# temp-stellwerk-a-3-autorouted.net
KiCad netlist of a schematic drawn in EAGLE
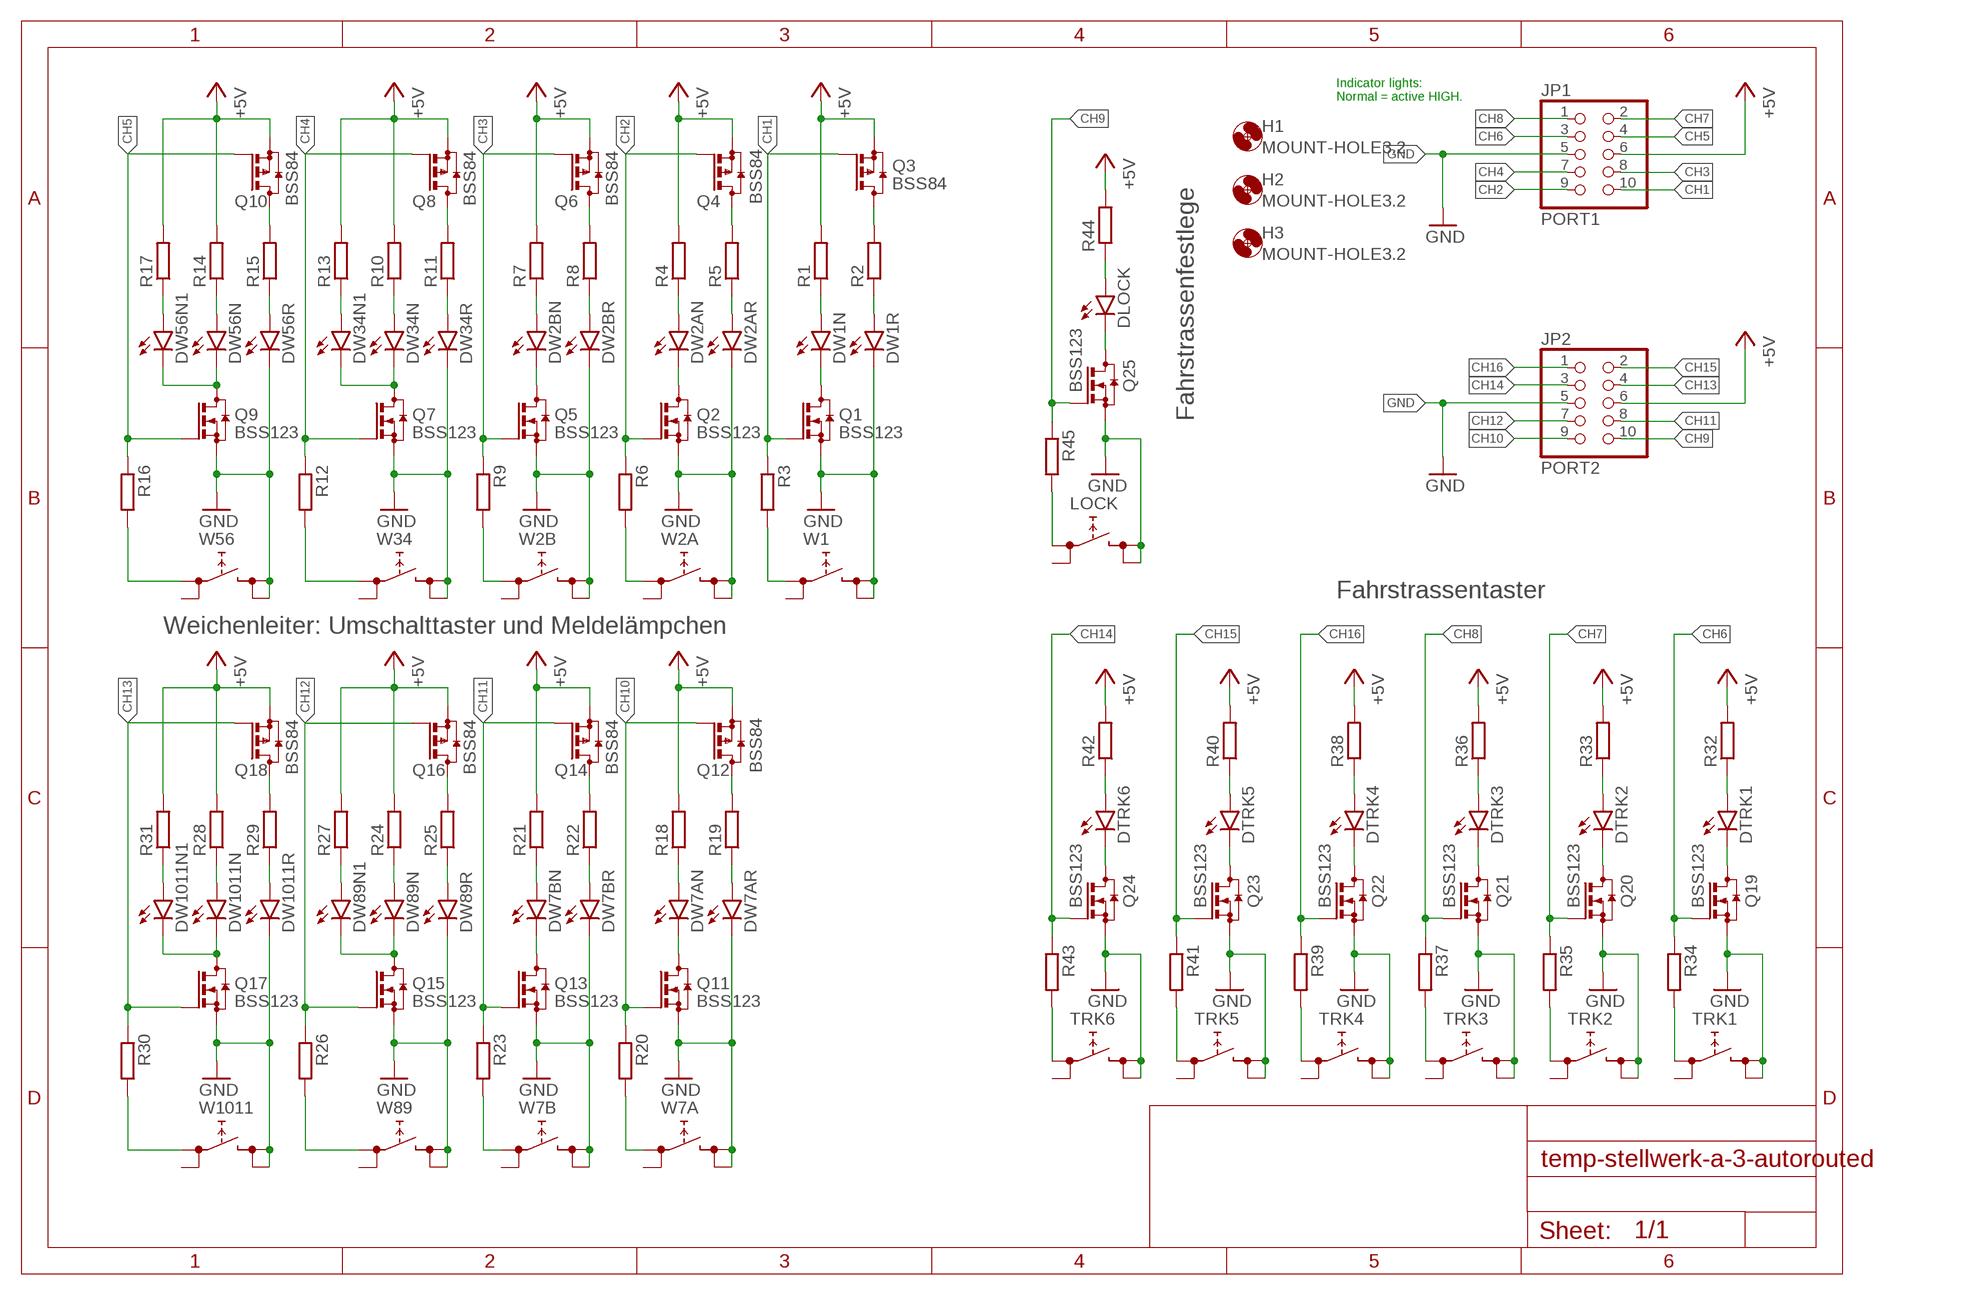
[diagram p0: schematic, sheet 1]

(export (version "E")
  (design (tool "Eeschema 10.0.6"))
  (components
    (comp (ref "DLOCK")
      (value "LEDCHIP-LED0805")
      (footprint "eagle-import:CHIP-LED0805")
      (libsource (lib "eagle-import") (part "LEDCHIP-LED0805"))
    )
    (comp (ref "DTRK1")
      (value "LEDCHIP-LED0805")
      (footprint "eagle-import:CHIP-LED0805")
      (libsource (lib "eagle-import") (part "LEDCHIP-LED0805"))
    )
    (comp (ref "DTRK2")
      (value "LEDCHIP-LED0805")
      (footprint "eagle-import:CHIP-LED0805")
      (libsource (lib "eagle-import") (part "LEDCHIP-LED0805"))
    )
    (comp (ref "DTRK3")
      (value "LEDCHIP-LED0805")
      (footprint "eagle-import:CHIP-LED0805")
      (libsource (lib "eagle-import") (part "LEDCHIP-LED0805"))
    )
    (comp (ref "DTRK4")
      (value "LEDCHIP-LED0805")
      (footprint "eagle-import:CHIP-LED0805")
      (libsource (lib "eagle-import") (part "LEDCHIP-LED0805"))
    )
    (comp (ref "DTRK5")
      (value "LEDCHIP-LED0805")
      (footprint "eagle-import:CHIP-LED0805")
      (libsource (lib "eagle-import") (part "LEDCHIP-LED0805"))
    )
    (comp (ref "DTRK6")
      (value "LEDCHIP-LED0805")
      (footprint "eagle-import:CHIP-LED0805")
      (libsource (lib "eagle-import") (part "LEDCHIP-LED0805"))
    )
    (comp (ref "DW1N")
      (value "LEDCHIP-LED0603")
      (footprint "eagle-import:CHIP-LED0603")
      (libsource (lib "eagle-import") (part "LEDCHIP-LED0603"))
    )
    (comp (ref "DW1R")
      (value "LEDCHIP-LED0603")
      (footprint "eagle-import:CHIP-LED0603")
      (libsource (lib "eagle-import") (part "LEDCHIP-LED0603"))
    )
    (comp (ref "DW2AN")
      (value "LEDCHIP-LED0603")
      (footprint "eagle-import:CHIP-LED0603")
      (libsource (lib "eagle-import") (part "LEDCHIP-LED0603"))
    )
    (comp (ref "DW2AR")
      (value "LEDCHIP-LED0603")
      (footprint "eagle-import:CHIP-LED0603")
      (libsource (lib "eagle-import") (part "LEDCHIP-LED0603"))
    )
    (comp (ref "DW2BN")
      (value "LEDCHIP-LED0805")
      (footprint "eagle-import:CHIP-LED0805")
      (libsource (lib "eagle-import") (part "LEDCHIP-LED0805"))
    )
    (comp (ref "DW2BR")
      (value "LEDCHIP-LED0805")
      (footprint "eagle-import:CHIP-LED0805")
      (libsource (lib "eagle-import") (part "LEDCHIP-LED0805"))
    )
    (comp (ref "DW7AN")
      (value "LEDCHIPLED_0603")
      (footprint "eagle-import:CHIPLED_0603")
      (libsource (lib "eagle-import") (part "LEDCHIPLED_0603"))
    )
    (comp (ref "DW7AR")
      (value "LEDCHIP-LED0603")
      (footprint "eagle-import:CHIP-LED0603")
      (libsource (lib "eagle-import") (part "LEDCHIP-LED0603"))
    )
    (comp (ref "DW7BN")
      (value "LEDCHIP-LED0805")
      (footprint "eagle-import:CHIP-LED0805")
      (libsource (lib "eagle-import") (part "LEDCHIP-LED0805"))
    )
    (comp (ref "DW7BR")
      (value "LEDCHIP-LED0805")
      (footprint "eagle-import:CHIP-LED0805")
      (libsource (lib "eagle-import") (part "LEDCHIP-LED0805"))
    )
    (comp (ref "DW34N")
      (value "LEDCHIP-LED0805")
      (footprint "eagle-import:CHIP-LED0805")
      (libsource (lib "eagle-import") (part "LEDCHIP-LED0805"))
    )
    (comp (ref "DW34N1")
      (value "LEDCHIP-LED0805")
      (footprint "eagle-import:CHIP-LED0805")
      (libsource (lib "eagle-import") (part "LEDCHIP-LED0805"))
    )
    (comp (ref "DW34R")
      (value "LEDCHIP-LED0805")
      (footprint "eagle-import:CHIP-LED0805")
      (libsource (lib "eagle-import") (part "LEDCHIP-LED0805"))
    )
    (comp (ref "DW56N")
      (value "LEDCHIP-LED0805")
      (footprint "eagle-import:CHIP-LED0805")
      (libsource (lib "eagle-import") (part "LEDCHIP-LED0805"))
    )
    (comp (ref "DW56N1")
      (value "LEDCHIP-LED0805")
      (footprint "eagle-import:CHIP-LED0805")
      (libsource (lib "eagle-import") (part "LEDCHIP-LED0805"))
    )
    (comp (ref "DW56R")
      (value "LEDCHIP-LED0805")
      (footprint "eagle-import:CHIP-LED0805")
      (libsource (lib "eagle-import") (part "LEDCHIP-LED0805"))
    )
    (comp (ref "DW89N")
      (value "LEDCHIP-LED0805")
      (footprint "eagle-import:CHIP-LED0805")
      (libsource (lib "eagle-import") (part "LEDCHIP-LED0805"))
    )
    (comp (ref "DW89N1")
      (value "LEDCHIP-LED0805")
      (footprint "eagle-import:CHIP-LED0805")
      (libsource (lib "eagle-import") (part "LEDCHIP-LED0805"))
    )
    (comp (ref "DW89R")
      (value "LEDCHIP-LED0805")
      (footprint "eagle-import:CHIP-LED0805")
      (libsource (lib "eagle-import") (part "LEDCHIP-LED0805"))
    )
    (comp (ref "DW1011N")
      (value "LEDCHIP-LED0805")
      (footprint "eagle-import:CHIP-LED0805")
      (libsource (lib "eagle-import") (part "LEDCHIP-LED0805"))
    )
    (comp (ref "DW1011N1")
      (value "LEDCHIP-LED0805")
      (footprint "eagle-import:CHIP-LED0805")
      (libsource (lib "eagle-import") (part "LEDCHIP-LED0805"))
    )
    (comp (ref "DW1011R")
      (value "LEDCHIP-LED0805")
      (footprint "eagle-import:CHIP-LED0805")
      (libsource (lib "eagle-import") (part "LEDCHIP-LED0805"))
    )
    (comp (ref "H1")
      (value "MOUNT-HOLE3.2")
      (footprint "eagle-import:3,2")
      (libsource (lib "eagle-import") (part "MOUNT-HOLE3.2"))
    )
    (comp (ref "H2")
      (value "MOUNT-HOLE3.2")
      (footprint "eagle-import:3,2")
      (libsource (lib "eagle-import") (part "MOUNT-HOLE3.2"))
    )
    (comp (ref "H3")
      (value "MOUNT-HOLE3.2")
      (footprint "eagle-import:3,2")
      (libsource (lib "eagle-import") (part "MOUNT-HOLE3.2"))
    )
    (comp (ref "JP1")
      (value "PORT1")
      (footprint "eagle-import:CON10M")
      (libsource (lib "eagle-import") (part "PINHD-2X5CN"))
    )
    (comp (ref "JP2")
      (value "PORT2")
      (footprint "eagle-import:CON10M")
      (libsource (lib "eagle-import") (part "PINHD-2X5CN"))
    )
    (comp (ref "LOCK")
      (value "LOCK")
      (footprint "eagle-import:TACTSW-6X6")
      (libsource (lib "eagle-import") (part "TACTSW-6X6S"))
    )
    (comp (ref "Q1")
      (value "BSS123")
      (footprint "eagle-import:SOT23-NCH")
      (libsource (lib "eagle-import") (part "BSS123"))
    )
    (comp (ref "Q2")
      (value "BSS123")
      (footprint "eagle-import:SOT23-NCH")
      (libsource (lib "eagle-import") (part "BSS123"))
    )
    (comp (ref "Q3")
      (value "BSS84")
      (footprint "eagle-import:SOT23")
      (libsource (lib "eagle-import") (part "BSS84"))
    )
    (comp (ref "Q4")
      (value "BSS84")
      (footprint "eagle-import:SOT23")
      (libsource (lib "eagle-import") (part "BSS84"))
    )
    (comp (ref "Q5")
      (value "BSS123")
      (footprint "eagle-import:SOT23-NCH")
      (libsource (lib "eagle-import") (part "BSS123"))
    )
    (comp (ref "Q6")
      (value "BSS84")
      (footprint "eagle-import:SOT23")
      (libsource (lib "eagle-import") (part "BSS84"))
    )
    (comp (ref "Q7")
      (value "BSS123")
      (footprint "eagle-import:SOT23-NCH")
      (libsource (lib "eagle-import") (part "BSS123"))
    )
    (comp (ref "Q8")
      (value "BSS84")
      (footprint "eagle-import:SOT23")
      (libsource (lib "eagle-import") (part "BSS84"))
    )
    (comp (ref "Q9")
      (value "BSS123")
      (footprint "eagle-import:SOT23-NCH")
      (libsource (lib "eagle-import") (part "BSS123"))
    )
    (comp (ref "Q10")
      (value "BSS84")
      (footprint "eagle-import:SOT23")
      (libsource (lib "eagle-import") (part "BSS84"))
    )
    (comp (ref "Q11")
      (value "BSS123")
      (footprint "eagle-import:SOT23-NCH")
      (libsource (lib "eagle-import") (part "BSS123"))
    )
    (comp (ref "Q12")
      (value "BSS84")
      (footprint "eagle-import:SOT23")
      (libsource (lib "eagle-import") (part "BSS84"))
    )
    (comp (ref "Q13")
      (value "BSS123")
      (footprint "eagle-import:SOT23-NCH")
      (libsource (lib "eagle-import") (part "BSS123"))
    )
    (comp (ref "Q14")
      (value "BSS84")
      (footprint "eagle-import:SOT23")
      (libsource (lib "eagle-import") (part "BSS84"))
    )
    (comp (ref "Q15")
      (value "BSS123")
      (footprint "eagle-import:SOT23-NCH")
      (libsource (lib "eagle-import") (part "BSS123"))
    )
    (comp (ref "Q16")
      (value "BSS84")
      (footprint "eagle-import:SOT23")
      (libsource (lib "eagle-import") (part "BSS84"))
    )
    (comp (ref "Q17")
      (value "BSS123")
      (footprint "eagle-import:SOT23-NCH")
      (libsource (lib "eagle-import") (part "BSS123"))
    )
    (comp (ref "Q18")
      (value "BSS84")
      (footprint "eagle-import:SOT23")
      (libsource (lib "eagle-import") (part "BSS84"))
    )
    (comp (ref "Q19")
      (value "BSS123")
      (footprint "eagle-import:SOT23-NCH")
      (libsource (lib "eagle-import") (part "BSS123"))
    )
    (comp (ref "Q20")
      (value "BSS123")
      (footprint "eagle-import:SOT23-NCH")
      (libsource (lib "eagle-import") (part "BSS123"))
    )
    (comp (ref "Q21")
      (value "BSS123")
      (footprint "eagle-import:SOT23-NCH")
      (libsource (lib "eagle-import") (part "BSS123"))
    )
    (comp (ref "Q22")
      (value "BSS123")
      (footprint "eagle-import:SOT23-NCH")
      (libsource (lib "eagle-import") (part "BSS123"))
    )
    (comp (ref "Q23")
      (value "BSS123")
      (footprint "eagle-import:SOT23-NCH")
      (libsource (lib "eagle-import") (part "BSS123"))
    )
    (comp (ref "Q24")
      (value "BSS123")
      (footprint "eagle-import:SOT23-NCH")
      (libsource (lib "eagle-import") (part "BSS123"))
    )
    (comp (ref "Q25")
      (value "BSS123")
      (footprint "eagle-import:SOT23-NCH")
      (libsource (lib "eagle-import") (part "BSS123"))
    )
    (comp (ref "R1")
      (value "R-EU_R0805")
      (footprint "eagle-import:R0805")
      (libsource (lib "eagle-import") (part "R-EU_R0805"))
    )
    (comp (ref "R2")
      (value "R-EU_R0805")
      (footprint "eagle-import:R0805")
      (libsource (lib "eagle-import") (part "R-EU_R0805"))
    )
    (comp (ref "R3")
      (value "R-EU_R0805")
      (footprint "eagle-import:R0805")
      (libsource (lib "eagle-import") (part "R-EU_R0805"))
    )
    (comp (ref "R4")
      (value "R-EU_R0805")
      (footprint "eagle-import:R0805")
      (libsource (lib "eagle-import") (part "R-EU_R0805"))
    )
    (comp (ref "R5")
      (value "R-EU_R0805")
      (footprint "eagle-import:R0805")
      (libsource (lib "eagle-import") (part "R-EU_R0805"))
    )
    (comp (ref "R6")
      (value "R-EU_R0805")
      (footprint "eagle-import:R0805")
      (libsource (lib "eagle-import") (part "R-EU_R0805"))
    )
    (comp (ref "R7")
      (value "R-EU_R0805")
      (footprint "eagle-import:R0805")
      (libsource (lib "eagle-import") (part "R-EU_R0805"))
    )
    (comp (ref "R8")
      (value "R-EU_R0805")
      (footprint "eagle-import:R0805")
      (libsource (lib "eagle-import") (part "R-EU_R0805"))
    )
    (comp (ref "R9")
      (value "R-EU_R0805")
      (footprint "eagle-import:R0805")
      (libsource (lib "eagle-import") (part "R-EU_R0805"))
    )
    (comp (ref "R10")
      (value "R-EU_R0805")
      (footprint "eagle-import:R0805")
      (libsource (lib "eagle-import") (part "R-EU_R0805"))
    )
    (comp (ref "R11")
      (value "R-EU_R0805")
      (footprint "eagle-import:R0805")
      (libsource (lib "eagle-import") (part "R-EU_R0805"))
    )
    (comp (ref "R12")
      (value "R-EU_R0805")
      (footprint "eagle-import:R0805")
      (libsource (lib "eagle-import") (part "R-EU_R0805"))
    )
    (comp (ref "R13")
      (value "R-EU_R0805")
      (footprint "eagle-import:R0805")
      (libsource (lib "eagle-import") (part "R-EU_R0805"))
    )
    (comp (ref "R14")
      (value "R-EU_R0805")
      (footprint "eagle-import:R0805")
      (libsource (lib "eagle-import") (part "R-EU_R0805"))
    )
    (comp (ref "R15")
      (value "R-EU_R0805")
      (footprint "eagle-import:R0805")
      (libsource (lib "eagle-import") (part "R-EU_R0805"))
    )
    (comp (ref "R16")
      (value "R-EU_R0805")
      (footprint "eagle-import:R0805")
      (libsource (lib "eagle-import") (part "R-EU_R0805"))
    )
    (comp (ref "R17")
      (value "R-EU_R0805")
      (footprint "eagle-import:R0805")
      (libsource (lib "eagle-import") (part "R-EU_R0805"))
    )
    (comp (ref "R18")
      (value "R-EU_R0805")
      (footprint "eagle-import:R0805")
      (libsource (lib "eagle-import") (part "R-EU_R0805"))
    )
    (comp (ref "R19")
      (value "R-EU_R0805")
      (footprint "eagle-import:R0805")
      (libsource (lib "eagle-import") (part "R-EU_R0805"))
    )
    (comp (ref "R20")
      (value "R-EU_R0805")
      (footprint "eagle-import:R0805")
      (libsource (lib "eagle-import") (part "R-EU_R0805"))
    )
    (comp (ref "R21")
      (value "R-EU_R0805")
      (footprint "eagle-import:R0805")
      (libsource (lib "eagle-import") (part "R-EU_R0805"))
    )
    (comp (ref "R22")
      (value "R-EU_R0805")
      (footprint "eagle-import:R0805")
      (libsource (lib "eagle-import") (part "R-EU_R0805"))
    )
    (comp (ref "R23")
      (value "R-EU_R0805")
      (footprint "eagle-import:R0805")
      (libsource (lib "eagle-import") (part "R-EU_R0805"))
    )
    (comp (ref "R24")
      (value "R-EU_R0805")
      (footprint "eagle-import:R0805")
      (libsource (lib "eagle-import") (part "R-EU_R0805"))
    )
    (comp (ref "R25")
      (value "R-EU_R0805")
      (footprint "eagle-import:R0805")
      (libsource (lib "eagle-import") (part "R-EU_R0805"))
    )
    (comp (ref "R26")
      (value "R-EU_R0805")
      (footprint "eagle-import:R0805")
      (libsource (lib "eagle-import") (part "R-EU_R0805"))
    )
    (comp (ref "R27")
      (value "R-EU_R0805")
      (footprint "eagle-import:R0805")
      (libsource (lib "eagle-import") (part "R-EU_R0805"))
    )
    (comp (ref "R28")
      (value "R-EU_R0805")
      (footprint "eagle-import:R0805")
      (libsource (lib "eagle-import") (part "R-EU_R0805"))
    )
    (comp (ref "R29")
      (value "R-EU_R0805")
      (footprint "eagle-import:R0805")
      (libsource (lib "eagle-import") (part "R-EU_R0805"))
    )
    (comp (ref "R30")
      (value "R-EU_R0805")
      (footprint "eagle-import:R0805")
      (libsource (lib "eagle-import") (part "R-EU_R0805"))
    )
    (comp (ref "R31")
      (value "R-EU_R0805")
      (footprint "eagle-import:R0805")
      (libsource (lib "eagle-import") (part "R-EU_R0805"))
    )
    (comp (ref "R32")
      (value "R-EU_R0805")
      (footprint "eagle-import:R0805")
      (libsource (lib "eagle-import") (part "R-EU_R0805"))
    )
    (comp (ref "R33")
      (value "R-EU_R0805")
      (footprint "eagle-import:R0805")
      (libsource (lib "eagle-import") (part "R-EU_R0805"))
    )
    (comp (ref "R34")
      (value "R-EU_R0805")
      (footprint "eagle-import:R0805")
      (libsource (lib "eagle-import") (part "R-EU_R0805"))
    )
    (comp (ref "R35")
      (value "R-EU_R0805")
      (footprint "eagle-import:R0805")
      (libsource (lib "eagle-import") (part "R-EU_R0805"))
    )
    (comp (ref "R36")
      (value "R-EU_R0805")
      (footprint "eagle-import:R0805")
      (libsource (lib "eagle-import") (part "R-EU_R0805"))
    )
    (comp (ref "R37")
      (value "R-EU_R0805")
      (footprint "eagle-import:R0805")
      (libsource (lib "eagle-import") (part "R-EU_R0805"))
    )
    (comp (ref "R38")
      (value "R-EU_R0805")
      (footprint "eagle-import:R0805")
      (libsource (lib "eagle-import") (part "R-EU_R0805"))
    )
    (comp (ref "R39")
      (value "R-EU_R0805")
      (footprint "eagle-import:R0805")
      (libsource (lib "eagle-import") (part "R-EU_R0805"))
    )
    (comp (ref "R40")
      (value "R-EU_R0805")
      (footprint "eagle-import:R0805")
      (libsource (lib "eagle-import") (part "R-EU_R0805"))
    )
    (comp (ref "R41")
      (value "R-EU_R0805")
      (footprint "eagle-import:R0805")
      (libsource (lib "eagle-import") (part "R-EU_R0805"))
    )
    (comp (ref "R42")
      (value "R-EU_R0805")
      (footprint "eagle-import:R0805")
      (libsource (lib "eagle-import") (part "R-EU_R0805"))
    )
    (comp (ref "R43")
      (value "R-EU_R0805")
      (footprint "eagle-import:R0805")
      (libsource (lib "eagle-import") (part "R-EU_R0805"))
    )
    (comp (ref "R44")
      (value "R-EU_R0805")
      (footprint "eagle-import:R0805")
      (libsource (lib "eagle-import") (part "R-EU_R0805"))
    )
    (comp (ref "R45")
      (value "R-EU_R0805")
      (footprint "eagle-import:R0805")
      (libsource (lib "eagle-import") (part "R-EU_R0805"))
    )
    (comp (ref "TRK1")
      (value "TACTSW-6X6S")
      (footprint "eagle-import:TACTSW-6X6")
      (libsource (lib "eagle-import") (part "TACTSW-6X6S"))
    )
    (comp (ref "TRK2")
      (value "TACTSW-6X6S")
      (footprint "eagle-import:TACTSW-6X6")
      (libsource (lib "eagle-import") (part "TACTSW-6X6S"))
    )
    (comp (ref "TRK3")
      (value "TACTSW-6X6S")
      (footprint "eagle-import:TACTSW-6X6")
      (libsource (lib "eagle-import") (part "TACTSW-6X6S"))
    )
    (comp (ref "TRK4")
      (value "TACTSW-6X6S")
      (footprint "eagle-import:TACTSW-6X6")
      (libsource (lib "eagle-import") (part "TACTSW-6X6S"))
    )
    (comp (ref "TRK5")
      (value "TACTSW-6X6S")
      (footprint "eagle-import:TACTSW-6X6")
      (libsource (lib "eagle-import") (part "TACTSW-6X6S"))
    )
    (comp (ref "TRK6")
      (value "TACTSW-6X6S")
      (footprint "eagle-import:TACTSW-6X6")
      (libsource (lib "eagle-import") (part "TACTSW-6X6S"))
    )
    (comp (ref "W1")
      (value "W1")
      (footprint "eagle-import:TACTSW-6X6")
      (libsource (lib "eagle-import") (part "TACTSW-6X6S"))
    )
    (comp (ref "W2A")
      (value "TACTSW-6X6S")
      (footprint "eagle-import:TACTSW-6X6")
      (libsource (lib "eagle-import") (part "TACTSW-6X6S"))
    )
    (comp (ref "W2B")
      (value "TACTSW-6X6S")
      (footprint "eagle-import:TACTSW-6X6")
      (libsource (lib "eagle-import") (part "TACTSW-6X6S"))
    )
    (comp (ref "W7A")
      (value "TACTSW-6X6S")
      (footprint "eagle-import:TACTSW-6X6")
      (libsource (lib "eagle-import") (part "TACTSW-6X6S"))
    )
    (comp (ref "W7B")
      (value "TACTSW-6X6S")
      (footprint "eagle-import:TACTSW-6X6")
      (libsource (lib "eagle-import") (part "TACTSW-6X6S"))
    )
    (comp (ref "W34")
      (value "XOVER")
      (footprint "eagle-import:TACTSW-6X6")
      (libsource (lib "eagle-import") (part "TACTSW-6X6S"))
    )
    (comp (ref "W56")
      (value "XOVER")
      (footprint "eagle-import:TACTSW-6X6")
      (libsource (lib "eagle-import") (part "TACTSW-6X6S"))
    )
    (comp (ref "W89")
      (value "XOVER")
      (footprint "eagle-import:TACTSW-6X6")
      (libsource (lib "eagle-import") (part "TACTSW-6X6S"))
    )
    (comp (ref "W1011")
      (value "XOVER")
      (footprint "eagle-import:TACTSW-6X6")
      (libsource (lib "eagle-import") (part "TACTSW-6X6S"))
    )
  )
  (nets
    (net (code "1") (name "+5V") (class "Default")
      (node (ref "JP1") (pin "6") (pinfunction "6_6") (pintype "passive"))
      (node (ref "JP2") (pin "6") (pinfunction "6_6") (pintype "passive"))
      (node (ref "Q10") (pin "2") (pinfunction "S_2") (pintype "passive"))
      (node (ref "Q12") (pin "2") (pinfunction "S_2") (pintype "passive"))
      (node (ref "Q14") (pin "2") (pinfunction "S_2") (pintype "passive"))
      (node (ref "Q16") (pin "2") (pinfunction "S_2") (pintype "passive"))
      (node (ref "Q18") (pin "2") (pinfunction "S_2") (pintype "passive"))
      (node (ref "Q3") (pin "2") (pinfunction "S_2") (pintype "passive"))
      (node (ref "Q4") (pin "2") (pinfunction "S_2") (pintype "passive"))
      (node (ref "Q6") (pin "2") (pinfunction "S_2") (pintype "passive"))
      (node (ref "Q8") (pin "2") (pinfunction "S_2") (pintype "passive"))
      (node (ref "R1") (pin "2") (pinfunction "2_2") (pintype "passive"))
      (node (ref "R10") (pin "2") (pinfunction "2_2") (pintype "passive"))
      (node (ref "R13") (pin "2") (pinfunction "2_2") (pintype "passive"))
      (node (ref "R14") (pin "2") (pinfunction "2_2") (pintype "passive"))
      (node (ref "R17") (pin "2") (pinfunction "2_2") (pintype "passive"))
      (node (ref "R18") (pin "2") (pinfunction "2_2") (pintype "passive"))
      (node (ref "R21") (pin "2") (pinfunction "2_2") (pintype "passive"))
      (node (ref "R24") (pin "2") (pinfunction "2_2") (pintype "passive"))
      (node (ref "R27") (pin "2") (pinfunction "2_2") (pintype "passive"))
      (node (ref "R28") (pin "2") (pinfunction "2_2") (pintype "passive"))
      (node (ref "R31") (pin "2") (pinfunction "2_2") (pintype "passive"))
      (node (ref "R32") (pin "2") (pinfunction "2_2") (pintype "passive"))
      (node (ref "R33") (pin "2") (pinfunction "2_2") (pintype "passive"))
      (node (ref "R36") (pin "2") (pinfunction "2_2") (pintype "passive"))
      (node (ref "R38") (pin "2") (pinfunction "2_2") (pintype "passive"))
      (node (ref "R4") (pin "2") (pinfunction "2_2") (pintype "passive"))
      (node (ref "R40") (pin "2") (pinfunction "2_2") (pintype "passive"))
      (node (ref "R42") (pin "2") (pinfunction "2_2") (pintype "passive"))
      (node (ref "R44") (pin "2") (pinfunction "2_2") (pintype "passive"))
      (node (ref "R7") (pin "2") (pinfunction "2_2") (pintype "passive"))
    )
    (net (code "2") (name "CH1") (class "Default")
      (node (ref "JP1") (pin "10") (pinfunction "10_10") (pintype "passive"))
      (node (ref "Q1") (pin "1") (pinfunction "G_1") (pintype "passive"))
      (node (ref "Q3") (pin "1") (pinfunction "G_1") (pintype "passive"))
      (node (ref "R3") (pin "1") (pinfunction "1_1") (pintype "passive"))
    )
    (net (code "3") (name "CH2") (class "Default")
      (node (ref "JP1") (pin "9") (pinfunction "9_9") (pintype "passive"))
      (node (ref "Q2") (pin "1") (pinfunction "G_1") (pintype "passive"))
      (node (ref "Q4") (pin "1") (pinfunction "G_1") (pintype "passive"))
      (node (ref "R6") (pin "1") (pinfunction "1_1") (pintype "passive"))
    )
    (net (code "4") (name "CH3") (class "Default")
      (node (ref "JP1") (pin "8") (pinfunction "8_8") (pintype "passive"))
      (node (ref "Q5") (pin "1") (pinfunction "G_1") (pintype "passive"))
      (node (ref "Q6") (pin "1") (pinfunction "G_1") (pintype "passive"))
      (node (ref "R9") (pin "1") (pinfunction "1_1") (pintype "passive"))
    )
    (net (code "5") (name "CH4") (class "Default")
      (node (ref "JP1") (pin "7") (pinfunction "7_7") (pintype "passive"))
      (node (ref "Q7") (pin "1") (pinfunction "G_1") (pintype "passive"))
      (node (ref "Q8") (pin "1") (pinfunction "G_1") (pintype "passive"))
      (node (ref "R12") (pin "1") (pinfunction "1_1") (pintype "passive"))
    )
    (net (code "6") (name "CH5") (class "Default")
      (node (ref "JP1") (pin "4") (pinfunction "4_4") (pintype "passive"))
      (node (ref "Q10") (pin "1") (pinfunction "G_1") (pintype "passive"))
      (node (ref "Q9") (pin "1") (pinfunction "G_1") (pintype "passive"))
      (node (ref "R16") (pin "1") (pinfunction "1_1") (pintype "passive"))
    )
    (net (code "7") (name "CH6") (class "Default")
      (node (ref "JP1") (pin "3") (pinfunction "3_3") (pintype "passive"))
      (node (ref "Q19") (pin "1") (pinfunction "G_1") (pintype "passive"))
      (node (ref "R34") (pin "1") (pinfunction "1_1") (pintype "passive"))
    )
    (net (code "8") (name "CH7") (class "Default")
      (node (ref "JP1") (pin "2") (pinfunction "2_2") (pintype "passive"))
      (node (ref "Q20") (pin "1") (pinfunction "G_1") (pintype "passive"))
      (node (ref "R35") (pin "1") (pinfunction "1_1") (pintype "passive"))
    )
    (net (code "9") (name "CH8") (class "Default")
      (node (ref "JP1") (pin "1") (pinfunction "1_1") (pintype "passive"))
      (node (ref "Q21") (pin "1") (pinfunction "G_1") (pintype "passive"))
      (node (ref "R37") (pin "1") (pinfunction "1_1") (pintype "passive"))
    )
    (net (code "10") (name "CH9") (class "Default")
      (node (ref "JP2") (pin "10") (pinfunction "10_10") (pintype "passive"))
      (node (ref "Q25") (pin "1") (pinfunction "G_1") (pintype "passive"))
      (node (ref "R45") (pin "1") (pinfunction "1_1") (pintype "passive"))
    )
    (net (code "11") (name "CH10") (class "Default")
      (node (ref "JP2") (pin "9") (pinfunction "9_9") (pintype "passive"))
      (node (ref "Q11") (pin "1") (pinfunction "G_1") (pintype "passive"))
      (node (ref "Q12") (pin "1") (pinfunction "G_1") (pintype "passive"))
      (node (ref "R20") (pin "1") (pinfunction "1_1") (pintype "passive"))
    )
    (net (code "12") (name "CH11") (class "Default")
      (node (ref "JP2") (pin "8") (pinfunction "8_8") (pintype "passive"))
      (node (ref "Q13") (pin "1") (pinfunction "G_1") (pintype "passive"))
      (node (ref "Q14") (pin "1") (pinfunction "G_1") (pintype "passive"))
      (node (ref "R23") (pin "1") (pinfunction "1_1") (pintype "passive"))
    )
    (net (code "13") (name "CH12") (class "Default")
      (node (ref "JP2") (pin "7") (pinfunction "7_7") (pintype "passive"))
      (node (ref "Q15") (pin "1") (pinfunction "G_1") (pintype "passive"))
      (node (ref "Q16") (pin "1") (pinfunction "G_1") (pintype "passive"))
      (node (ref "R26") (pin "1") (pinfunction "1_1") (pintype "passive"))
    )
    (net (code "14") (name "CH13") (class "Default")
      (node (ref "JP2") (pin "4") (pinfunction "4_4") (pintype "passive"))
      (node (ref "Q17") (pin "1") (pinfunction "G_1") (pintype "passive"))
      (node (ref "Q18") (pin "1") (pinfunction "G_1") (pintype "passive"))
      (node (ref "R30") (pin "1") (pinfunction "1_1") (pintype "passive"))
    )
    (net (code "15") (name "CH14") (class "Default")
      (node (ref "JP2") (pin "3") (pinfunction "3_3") (pintype "passive"))
      (node (ref "Q24") (pin "1") (pinfunction "G_1") (pintype "passive"))
      (node (ref "R43") (pin "1") (pinfunction "1_1") (pintype "passive"))
    )
    (net (code "16") (name "CH15") (class "Default")
      (node (ref "JP2") (pin "2") (pinfunction "2_2") (pintype "passive"))
      (node (ref "Q23") (pin "1") (pinfunction "G_1") (pintype "passive"))
      (node (ref "R41") (pin "1") (pinfunction "1_1") (pintype "passive"))
    )
    (net (code "17") (name "CH16") (class "Default")
      (node (ref "JP2") (pin "1") (pinfunction "1_1") (pintype "passive"))
      (node (ref "Q22") (pin "1") (pinfunction "G_1") (pintype "passive"))
      (node (ref "R39") (pin "1") (pinfunction "1_1") (pintype "passive"))
    )
    (net (code "18") (name "GND") (class "Default")
      (node (ref "DW1011R") (pin "C") (pinfunction "C_C") (pintype "passive"))
      (node (ref "DW1R") (pin "C") (pinfunction "C_C") (pintype "passive"))
      (node (ref "DW2AR") (pin "C") (pinfunction "C_C") (pintype "passive"))
      (node (ref "DW2BR") (pin "C") (pinfunction "C_C") (pintype "passive"))
      (node (ref "DW34R") (pin "C") (pinfunction "C_C") (pintype "passive"))
      (node (ref "DW56R") (pin "C") (pinfunction "C_C") (pintype "passive"))
      (node (ref "DW7AR") (pin "C") (pinfunction "C_C") (pintype "passive"))
      (node (ref "DW7BR") (pin "C") (pinfunction "C_C") (pintype "passive"))
      (node (ref "DW89R") (pin "C") (pinfunction "C_C") (pintype "passive"))
      (node (ref "JP1") (pin "5") (pinfunction "5_5") (pintype "passive"))
      (node (ref "JP2") (pin "5") (pinfunction "5_5") (pintype "passive"))
      (node (ref "LOCK") (pin "3") (pinfunction "2.1_3") (pintype "passive"))
      (node (ref "LOCK") (pin "4") (pinfunction "2.2_4") (pintype "passive"))
      (node (ref "Q1") (pin "2") (pinfunction "S_2") (pintype "passive"))
      (node (ref "Q11") (pin "2") (pinfunction "S_2") (pintype "passive"))
      (node (ref "Q13") (pin "2") (pinfunction "S_2") (pintype "passive"))
      (node (ref "Q15") (pin "2") (pinfunction "S_2") (pintype "passive"))
      (node (ref "Q17") (pin "2") (pinfunction "S_2") (pintype "passive"))
      (node (ref "Q19") (pin "2") (pinfunction "S_2") (pintype "passive"))
      (node (ref "Q2") (pin "2") (pinfunction "S_2") (pintype "passive"))
      (node (ref "Q20") (pin "2") (pinfunction "S_2") (pintype "passive"))
      (node (ref "Q21") (pin "2") (pinfunction "S_2") (pintype "passive"))
      (node (ref "Q22") (pin "2") (pinfunction "S_2") (pintype "passive"))
      (node (ref "Q23") (pin "2") (pinfunction "S_2") (pintype "passive"))
      (node (ref "Q24") (pin "2") (pinfunction "S_2") (pintype "passive"))
      (node (ref "Q25") (pin "2") (pinfunction "S_2") (pintype "passive"))
      (node (ref "Q5") (pin "2") (pinfunction "S_2") (pintype "passive"))
      (node (ref "Q7") (pin "2") (pinfunction "S_2") (pintype "passive"))
      (node (ref "Q9") (pin "2") (pinfunction "S_2") (pintype "passive"))
      (node (ref "TRK1") (pin "3") (pinfunction "2.1_3") (pintype "passive"))
      (node (ref "TRK1") (pin "4") (pinfunction "2.2_4") (pintype "passive"))
      (node (ref "TRK2") (pin "3") (pinfunction "2.1_3") (pintype "passive"))
      (node (ref "TRK2") (pin "4") (pinfunction "2.2_4") (pintype "passive"))
      (node (ref "TRK3") (pin "3") (pinfunction "2.1_3") (pintype "passive"))
      (node (ref "TRK3") (pin "4") (pinfunction "2.2_4") (pintype "passive"))
      (node (ref "TRK4") (pin "3") (pinfunction "2.1_3") (pintype "passive"))
      (node (ref "TRK4") (pin "4") (pinfunction "2.2_4") (pintype "passive"))
      (node (ref "TRK5") (pin "3") (pinfunction "2.1_3") (pintype "passive"))
      (node (ref "TRK5") (pin "4") (pinfunction "2.2_4") (pintype "passive"))
      (node (ref "TRK6") (pin "3") (pinfunction "2.1_3") (pintype "passive"))
      (node (ref "TRK6") (pin "4") (pinfunction "2.2_4") (pintype "passive"))
      (node (ref "W1") (pin "3") (pinfunction "2.1_3") (pintype "passive"))
      (node (ref "W1") (pin "4") (pinfunction "2.2_4") (pintype "passive"))
      (node (ref "W1011") (pin "3") (pinfunction "2.1_3") (pintype "passive"))
      (node (ref "W1011") (pin "4") (pinfunction "2.2_4") (pintype "passive"))
      (node (ref "W2A") (pin "3") (pinfunction "2.1_3") (pintype "passive"))
      (node (ref "W2A") (pin "4") (pinfunction "2.2_4") (pintype "passive"))
      (node (ref "W2B") (pin "3") (pinfunction "2.1_3") (pintype "passive"))
      (node (ref "W2B") (pin "4") (pinfunction "2.2_4") (pintype "passive"))
      (node (ref "W34") (pin "3") (pinfunction "2.1_3") (pintype "passive"))
      (node (ref "W34") (pin "4") (pinfunction "2.2_4") (pintype "passive"))
      (node (ref "W56") (pin "3") (pinfunction "2.1_3") (pintype "passive"))
      (node (ref "W56") (pin "4") (pinfunction "2.2_4") (pintype "passive"))
      (node (ref "W7A") (pin "3") (pinfunction "2.1_3") (pintype "passive"))
      (node (ref "W7A") (pin "4") (pinfunction "2.2_4") (pintype "passive"))
      (node (ref "W7B") (pin "3") (pinfunction "2.1_3") (pintype "passive"))
      (node (ref "W7B") (pin "4") (pinfunction "2.2_4") (pintype "passive"))
      (node (ref "W89") (pin "3") (pinfunction "2.1_3") (pintype "passive"))
      (node (ref "W89") (pin "4") (pinfunction "2.2_4") (pintype "passive"))
    )
    (net (code "19") (name "Net-(DLOCK-PadA)") (class "Default")
      (node (ref "DLOCK") (pin "A") (pinfunction "A_A") (pintype "passive"))
      (node (ref "R44") (pin "1") (pinfunction "1_1") (pintype "passive"))
    )
    (net (code "20") (name "Net-(DTRK1-PadA)") (class "Default")
      (node (ref "DTRK1") (pin "A") (pinfunction "A_A") (pintype "passive"))
      (node (ref "R32") (pin "1") (pinfunction "1_1") (pintype "passive"))
    )
    (net (code "21") (name "Net-(DTRK2-PadA)") (class "Default")
      (node (ref "DTRK2") (pin "A") (pinfunction "A_A") (pintype "passive"))
      (node (ref "R33") (pin "1") (pinfunction "1_1") (pintype "passive"))
    )
    (net (code "22") (name "Net-(DTRK3-PadA)") (class "Default")
      (node (ref "DTRK3") (pin "A") (pinfunction "A_A") (pintype "passive"))
      (node (ref "R36") (pin "1") (pinfunction "1_1") (pintype "passive"))
    )
    (net (code "23") (name "Net-(DTRK4-PadA)") (class "Default")
      (node (ref "DTRK4") (pin "A") (pinfunction "A_A") (pintype "passive"))
      (node (ref "R38") (pin "1") (pinfunction "1_1") (pintype "passive"))
    )
    (net (code "24") (name "Net-(DTRK5-PadA)") (class "Default")
      (node (ref "DTRK5") (pin "A") (pinfunction "A_A") (pintype "passive"))
      (node (ref "R40") (pin "1") (pinfunction "1_1") (pintype "passive"))
    )
    (net (code "25") (name "Net-(DTRK6-PadA)") (class "Default")
      (node (ref "DTRK6") (pin "A") (pinfunction "A_A") (pintype "passive"))
      (node (ref "R42") (pin "1") (pinfunction "1_1") (pintype "passive"))
    )
    (net (code "26") (name "Net-(DW1N-PadA)") (class "Default")
      (node (ref "DW1N") (pin "A") (pinfunction "A_A") (pintype "passive"))
      (node (ref "R1") (pin "1") (pinfunction "1_1") (pintype "passive"))
    )
    (net (code "27") (name "Net-(DW1R-PadA)") (class "Default")
      (node (ref "DW1R") (pin "A") (pinfunction "A_A") (pintype "passive"))
      (node (ref "R2") (pin "1") (pinfunction "1_1") (pintype "passive"))
    )
    (net (code "28") (name "Net-(DW2AN-PadA)") (class "Default")
      (node (ref "DW2AN") (pin "A") (pinfunction "A_A") (pintype "passive"))
      (node (ref "R4") (pin "1") (pinfunction "1_1") (pintype "passive"))
    )
    (net (code "29") (name "Net-(DW2AR-PadA)") (class "Default")
      (node (ref "DW2AR") (pin "A") (pinfunction "A_A") (pintype "passive"))
      (node (ref "R5") (pin "1") (pinfunction "1_1") (pintype "passive"))
    )
    (net (code "30") (name "Net-(DW2BN-PadA)") (class "Default")
      (node (ref "DW2BN") (pin "A") (pinfunction "A_A") (pintype "passive"))
      (node (ref "R7") (pin "1") (pinfunction "1_1") (pintype "passive"))
    )
    (net (code "31") (name "Net-(DW2BR-PadA)") (class "Default")
      (node (ref "DW2BR") (pin "A") (pinfunction "A_A") (pintype "passive"))
      (node (ref "R8") (pin "1") (pinfunction "1_1") (pintype "passive"))
    )
    (net (code "32") (name "Net-(DW7AN-PadA)") (class "Default")
      (node (ref "DW7AN") (pin "A") (pinfunction "A_A") (pintype "passive"))
      (node (ref "R18") (pin "1") (pinfunction "1_1") (pintype "passive"))
    )
    (net (code "33") (name "Net-(DW7AR-PadA)") (class "Default")
      (node (ref "DW7AR") (pin "A") (pinfunction "A_A") (pintype "passive"))
      (node (ref "R19") (pin "1") (pinfunction "1_1") (pintype "passive"))
    )
    (net (code "34") (name "Net-(DW7BN-PadA)") (class "Default")
      (node (ref "DW7BN") (pin "A") (pinfunction "A_A") (pintype "passive"))
      (node (ref "R21") (pin "1") (pinfunction "1_1") (pintype "passive"))
    )
    (net (code "35") (name "Net-(DW7BR-PadA)") (class "Default")
      (node (ref "DW7BR") (pin "A") (pinfunction "A_A") (pintype "passive"))
      (node (ref "R22") (pin "1") (pinfunction "1_1") (pintype "passive"))
    )
    (net (code "36") (name "Net-(DW34N-PadA)") (class "Default")
      (node (ref "DW34N") (pin "A") (pinfunction "A_A") (pintype "passive"))
      (node (ref "R10") (pin "1") (pinfunction "1_1") (pintype "passive"))
    )
    (net (code "37") (name "Net-(DW34N1-PadA)") (class "Default")
      (node (ref "DW34N1") (pin "A") (pinfunction "A_A") (pintype "passive"))
      (node (ref "R13") (pin "1") (pinfunction "1_1") (pintype "passive"))
    )
    (net (code "38") (name "Net-(DW34R-PadA)") (class "Default")
      (node (ref "DW34R") (pin "A") (pinfunction "A_A") (pintype "passive"))
      (node (ref "R11") (pin "1") (pinfunction "1_1") (pintype "passive"))
    )
    (net (code "39") (name "Net-(DW56N-PadA)") (class "Default")
      (node (ref "DW56N") (pin "A") (pinfunction "A_A") (pintype "passive"))
      (node (ref "R14") (pin "1") (pinfunction "1_1") (pintype "passive"))
    )
    (net (code "40") (name "Net-(DW56N1-PadA)") (class "Default")
      (node (ref "DW56N1") (pin "A") (pinfunction "A_A") (pintype "passive"))
      (node (ref "R17") (pin "1") (pinfunction "1_1") (pintype "passive"))
    )
    (net (code "41") (name "Net-(DW56R-PadA)") (class "Default")
      (node (ref "DW56R") (pin "A") (pinfunction "A_A") (pintype "passive"))
      (node (ref "R15") (pin "1") (pinfunction "1_1") (pintype "passive"))
    )
    (net (code "42") (name "Net-(DW89N-PadA)") (class "Default")
      (node (ref "DW89N") (pin "A") (pinfunction "A_A") (pintype "passive"))
      (node (ref "R24") (pin "1") (pinfunction "1_1") (pintype "passive"))
    )
    (net (code "43") (name "Net-(DW89N1-PadA)") (class "Default")
      (node (ref "DW89N1") (pin "A") (pinfunction "A_A") (pintype "passive"))
      (node (ref "R27") (pin "1") (pinfunction "1_1") (pintype "passive"))
    )
    (net (code "44") (name "Net-(DW89R-PadA)") (class "Default")
      (node (ref "DW89R") (pin "A") (pinfunction "A_A") (pintype "passive"))
      (node (ref "R25") (pin "1") (pinfunction "1_1") (pintype "passive"))
    )
    (net (code "45") (name "Net-(DW1011N-PadA)") (class "Default")
      (node (ref "DW1011N") (pin "A") (pinfunction "A_A") (pintype "passive"))
      (node (ref "R28") (pin "1") (pinfunction "1_1") (pintype "passive"))
    )
    (net (code "46") (name "Net-(DW1011N1-PadA)") (class "Default")
      (node (ref "DW1011N1") (pin "A") (pinfunction "A_A") (pintype "passive"))
      (node (ref "R31") (pin "1") (pinfunction "1_1") (pintype "passive"))
    )
    (net (code "47") (name "Net-(DW1011R-PadA)") (class "Default")
      (node (ref "DW1011R") (pin "A") (pinfunction "A_A") (pintype "passive"))
      (node (ref "R29") (pin "1") (pinfunction "1_1") (pintype "passive"))
    )
    (net (code "48") (name "Net-(LOCK-1.1)") (class "Default")
      (node (ref "LOCK") (pin "1") (pinfunction "1.1_1") (pintype "passive"))
      (node (ref "R45") (pin "2") (pinfunction "2_2") (pintype "passive"))
    )
    (net (code "49") (name "Net-(Q1-D)") (class "Default")
      (node (ref "DW1N") (pin "C") (pinfunction "C_C") (pintype "passive"))
      (node (ref "Q1") (pin "3") (pinfunction "D_3") (pintype "passive"))
    )
    (net (code "50") (name "Net-(Q2-D)") (class "Default")
      (node (ref "DW2AN") (pin "C") (pinfunction "C_C") (pintype "passive"))
      (node (ref "Q2") (pin "3") (pinfunction "D_3") (pintype "passive"))
    )
    (net (code "51") (name "Net-(Q3-D)") (class "Default")
      (node (ref "Q3") (pin "3") (pinfunction "D_3") (pintype "passive"))
      (node (ref "R2") (pin "2") (pinfunction "2_2") (pintype "passive"))
    )
    (net (code "52") (name "Net-(Q4-D)") (class "Default")
      (node (ref "Q4") (pin "3") (pinfunction "D_3") (pintype "passive"))
      (node (ref "R5") (pin "2") (pinfunction "2_2") (pintype "passive"))
    )
    (net (code "53") (name "Net-(Q5-D)") (class "Default")
      (node (ref "DW2BN") (pin "C") (pinfunction "C_C") (pintype "passive"))
      (node (ref "Q5") (pin "3") (pinfunction "D_3") (pintype "passive"))
    )
    (net (code "54") (name "Net-(Q6-D)") (class "Default")
      (node (ref "Q6") (pin "3") (pinfunction "D_3") (pintype "passive"))
      (node (ref "R8") (pin "2") (pinfunction "2_2") (pintype "passive"))
    )
    (net (code "55") (name "Net-(Q7-D)") (class "Default")
      (node (ref "DW34N") (pin "C") (pinfunction "C_C") (pintype "passive"))
      (node (ref "DW34N1") (pin "C") (pinfunction "C_C") (pintype "passive"))
      (node (ref "Q7") (pin "3") (pinfunction "D_3") (pintype "passive"))
    )
    (net (code "56") (name "Net-(Q8-D)") (class "Default")
      (node (ref "Q8") (pin "3") (pinfunction "D_3") (pintype "passive"))
      (node (ref "R11") (pin "2") (pinfunction "2_2") (pintype "passive"))
    )
    (net (code "57") (name "Net-(Q9-D)") (class "Default")
      (node (ref "DW56N") (pin "C") (pinfunction "C_C") (pintype "passive"))
      (node (ref "DW56N1") (pin "C") (pinfunction "C_C") (pintype "passive"))
      (node (ref "Q9") (pin "3") (pinfunction "D_3") (pintype "passive"))
    )
    (net (code "58") (name "Net-(Q10-D)") (class "Default")
      (node (ref "Q10") (pin "3") (pinfunction "D_3") (pintype "passive"))
      (node (ref "R15") (pin "2") (pinfunction "2_2") (pintype "passive"))
    )
    (net (code "59") (name "Net-(Q11-D)") (class "Default")
      (node (ref "DW7AN") (pin "C") (pinfunction "C_C") (pintype "passive"))
      (node (ref "Q11") (pin "3") (pinfunction "D_3") (pintype "passive"))
    )
    (net (code "60") (name "Net-(Q12-D)") (class "Default")
      (node (ref "Q12") (pin "3") (pinfunction "D_3") (pintype "passive"))
      (node (ref "R19") (pin "2") (pinfunction "2_2") (pintype "passive"))
    )
    (net (code "61") (name "Net-(Q13-D)") (class "Default")
      (node (ref "DW7BN") (pin "C") (pinfunction "C_C") (pintype "passive"))
      (node (ref "Q13") (pin "3") (pinfunction "D_3") (pintype "passive"))
    )
    (net (code "62") (name "Net-(Q14-D)") (class "Default")
      (node (ref "Q14") (pin "3") (pinfunction "D_3") (pintype "passive"))
      (node (ref "R22") (pin "2") (pinfunction "2_2") (pintype "passive"))
    )
    (net (code "63") (name "Net-(Q15-D)") (class "Default")
      (node (ref "DW89N") (pin "C") (pinfunction "C_C") (pintype "passive"))
      (node (ref "DW89N1") (pin "C") (pinfunction "C_C") (pintype "passive"))
      (node (ref "Q15") (pin "3") (pinfunction "D_3") (pintype "passive"))
    )
    (net (code "64") (name "Net-(Q16-D)") (class "Default")
      (node (ref "Q16") (pin "3") (pinfunction "D_3") (pintype "passive"))
      (node (ref "R25") (pin "2") (pinfunction "2_2") (pintype "passive"))
    )
    (net (code "65") (name "Net-(Q17-D)") (class "Default")
      (node (ref "DW1011N") (pin "C") (pinfunction "C_C") (pintype "passive"))
      (node (ref "DW1011N1") (pin "C") (pinfunction "C_C") (pintype "passive"))
      (node (ref "Q17") (pin "3") (pinfunction "D_3") (pintype "passive"))
    )
    (net (code "66") (name "Net-(Q18-D)") (class "Default")
      (node (ref "Q18") (pin "3") (pinfunction "D_3") (pintype "passive"))
      (node (ref "R29") (pin "2") (pinfunction "2_2") (pintype "passive"))
    )
    (net (code "67") (name "Net-(Q19-D)") (class "Default")
      (node (ref "DTRK1") (pin "C") (pinfunction "C_C") (pintype "passive"))
      (node (ref "Q19") (pin "3") (pinfunction "D_3") (pintype "passive"))
    )
    (net (code "68") (name "Net-(Q20-D)") (class "Default")
      (node (ref "DTRK2") (pin "C") (pinfunction "C_C") (pintype "passive"))
      (node (ref "Q20") (pin "3") (pinfunction "D_3") (pintype "passive"))
    )
    (net (code "69") (name "Net-(Q21-D)") (class "Default")
      (node (ref "DTRK3") (pin "C") (pinfunction "C_C") (pintype "passive"))
      (node (ref "Q21") (pin "3") (pinfunction "D_3") (pintype "passive"))
    )
    (net (code "70") (name "Net-(Q22-D)") (class "Default")
      (node (ref "DTRK4") (pin "C") (pinfunction "C_C") (pintype "passive"))
      (node (ref "Q22") (pin "3") (pinfunction "D_3") (pintype "passive"))
    )
    (net (code "71") (name "Net-(Q23-D)") (class "Default")
      (node (ref "DTRK5") (pin "C") (pinfunction "C_C") (pintype "passive"))
      (node (ref "Q23") (pin "3") (pinfunction "D_3") (pintype "passive"))
    )
    (net (code "72") (name "Net-(Q24-D)") (class "Default")
      (node (ref "DTRK6") (pin "C") (pinfunction "C_C") (pintype "passive"))
      (node (ref "Q24") (pin "3") (pinfunction "D_3") (pintype "passive"))
    )
    (net (code "73") (name "Net-(Q25-D)") (class "Default")
      (node (ref "DLOCK") (pin "C") (pinfunction "C_C") (pintype "passive"))
      (node (ref "Q25") (pin "3") (pinfunction "D_3") (pintype "passive"))
    )
    (net (code "74") (name "Net-(TRK1-1.1)") (class "Default")
      (node (ref "R34") (pin "2") (pinfunction "2_2") (pintype "passive"))
      (node (ref "TRK1") (pin "1") (pinfunction "1.1_1") (pintype "passive"))
    )
    (net (code "75") (name "Net-(TRK2-1.1)") (class "Default")
      (node (ref "R35") (pin "2") (pinfunction "2_2") (pintype "passive"))
      (node (ref "TRK2") (pin "1") (pinfunction "1.1_1") (pintype "passive"))
    )
    (net (code "76") (name "Net-(TRK3-1.1)") (class "Default")
      (node (ref "R37") (pin "2") (pinfunction "2_2") (pintype "passive"))
      (node (ref "TRK3") (pin "1") (pinfunction "1.1_1") (pintype "passive"))
    )
    (net (code "77") (name "Net-(TRK4-1.1)") (class "Default")
      (node (ref "R39") (pin "2") (pinfunction "2_2") (pintype "passive"))
      (node (ref "TRK4") (pin "1") (pinfunction "1.1_1") (pintype "passive"))
    )
    (net (code "78") (name "Net-(TRK5-1.1)") (class "Default")
      (node (ref "R41") (pin "2") (pinfunction "2_2") (pintype "passive"))
      (node (ref "TRK5") (pin "1") (pinfunction "1.1_1") (pintype "passive"))
    )
    (net (code "79") (name "Net-(TRK6-1.1)") (class "Default")
      (node (ref "R43") (pin "2") (pinfunction "2_2") (pintype "passive"))
      (node (ref "TRK6") (pin "1") (pinfunction "1.1_1") (pintype "passive"))
    )
    (net (code "80") (name "Net-(W1-1.1)") (class "Default")
      (node (ref "R3") (pin "2") (pinfunction "2_2") (pintype "passive"))
      (node (ref "W1") (pin "1") (pinfunction "1.1_1") (pintype "passive"))
    )
    (net (code "81") (name "Net-(W2A-1.1)") (class "Default")
      (node (ref "R6") (pin "2") (pinfunction "2_2") (pintype "passive"))
      (node (ref "W2A") (pin "1") (pinfunction "1.1_1") (pintype "passive"))
    )
    (net (code "82") (name "Net-(W2B-1.1)") (class "Default")
      (node (ref "R9") (pin "2") (pinfunction "2_2") (pintype "passive"))
      (node (ref "W2B") (pin "1") (pinfunction "1.1_1") (pintype "passive"))
    )
    (net (code "83") (name "Net-(W7A-1.1)") (class "Default")
      (node (ref "R20") (pin "2") (pinfunction "2_2") (pintype "passive"))
      (node (ref "W7A") (pin "1") (pinfunction "1.1_1") (pintype "passive"))
    )
    (net (code "84") (name "Net-(W7B-1.1)") (class "Default")
      (node (ref "R23") (pin "2") (pinfunction "2_2") (pintype "passive"))
      (node (ref "W7B") (pin "1") (pinfunction "1.1_1") (pintype "passive"))
    )
    (net (code "85") (name "Net-(W34-1.1)") (class "Default")
      (node (ref "R12") (pin "2") (pinfunction "2_2") (pintype "passive"))
      (node (ref "W34") (pin "1") (pinfunction "1.1_1") (pintype "passive"))
    )
    (net (code "86") (name "Net-(W56-1.1)") (class "Default")
      (node (ref "R16") (pin "2") (pinfunction "2_2") (pintype "passive"))
      (node (ref "W56") (pin "1") (pinfunction "1.1_1") (pintype "passive"))
    )
    (net (code "87") (name "Net-(W89-1.1)") (class "Default")
      (node (ref "R26") (pin "2") (pinfunction "2_2") (pintype "passive"))
      (node (ref "W89") (pin "1") (pinfunction "1.1_1") (pintype "passive"))
    )
    (net (code "88") (name "Net-(W1011-1.1)") (class "Default")
      (node (ref "R30") (pin "2") (pinfunction "2_2") (pintype "passive"))
      (node (ref "W1011") (pin "1") (pinfunction "1.1_1") (pintype "passive"))
    )
    (net (code "89") (name "unconnected-(LOCK-1.2-Pad2)") (class "Default")
      (node (ref "LOCK") (pin "2") (pinfunction "1.2_2") (pintype "passive"))
    )
    (net (code "90") (name "unconnected-(TRK1-1.2-Pad2)") (class "Default")
      (node (ref "TRK1") (pin "2") (pinfunction "1.2_2") (pintype "passive"))
    )
    (net (code "91") (name "unconnected-(TRK2-1.2-Pad2)") (class "Default")
      (node (ref "TRK2") (pin "2") (pinfunction "1.2_2") (pintype "passive"))
    )
    (net (code "92") (name "unconnected-(TRK3-1.2-Pad2)") (class "Default")
      (node (ref "TRK3") (pin "2") (pinfunction "1.2_2") (pintype "passive"))
    )
    (net (code "93") (name "unconnected-(TRK4-1.2-Pad2)") (class "Default")
      (node (ref "TRK4") (pin "2") (pinfunction "1.2_2") (pintype "passive"))
    )
    (net (code "94") (name "unconnected-(TRK5-1.2-Pad2)") (class "Default")
      (node (ref "TRK5") (pin "2") (pinfunction "1.2_2") (pintype "passive"))
    )
    (net (code "95") (name "unconnected-(TRK6-1.2-Pad2)") (class "Default")
      (node (ref "TRK6") (pin "2") (pinfunction "1.2_2") (pintype "passive"))
    )
    (net (code "96") (name "unconnected-(W1-1.2-Pad2)") (class "Default")
      (node (ref "W1") (pin "2") (pinfunction "1.2_2") (pintype "passive"))
    )
    (net (code "97") (name "unconnected-(W2A-1.2-Pad2)") (class "Default")
      (node (ref "W2A") (pin "2") (pinfunction "1.2_2") (pintype "passive"))
    )
    (net (code "98") (name "unconnected-(W2B-1.2-Pad2)") (class "Default")
      (node (ref "W2B") (pin "2") (pinfunction "1.2_2") (pintype "passive"))
    )
    (net (code "99") (name "unconnected-(W7A-1.2-Pad2)") (class "Default")
      (node (ref "W7A") (pin "2") (pinfunction "1.2_2") (pintype "passive"))
    )
    (net (code "100") (name "unconnected-(W7B-1.2-Pad2)") (class "Default")
      (node (ref "W7B") (pin "2") (pinfunction "1.2_2") (pintype "passive"))
    )
    (net (code "101") (name "unconnected-(W34-1.2-Pad2)") (class "Default")
      (node (ref "W34") (pin "2") (pinfunction "1.2_2") (pintype "passive"))
    )
    (net (code "102") (name "unconnected-(W56-1.2-Pad2)") (class "Default")
      (node (ref "W56") (pin "2") (pinfunction "1.2_2") (pintype "passive"))
    )
    (net (code "103") (name "unconnected-(W89-1.2-Pad2)") (class "Default")
      (node (ref "W89") (pin "2") (pinfunction "1.2_2") (pintype "passive"))
    )
    (net (code "104") (name "unconnected-(W1011-1.2-Pad2)") (class "Default")
      (node (ref "W1011") (pin "2") (pinfunction "1.2_2") (pintype "passive"))
    )
  )
)
